# EC60_1.net
KiCad netlist of a schematic drawn in EAGLE
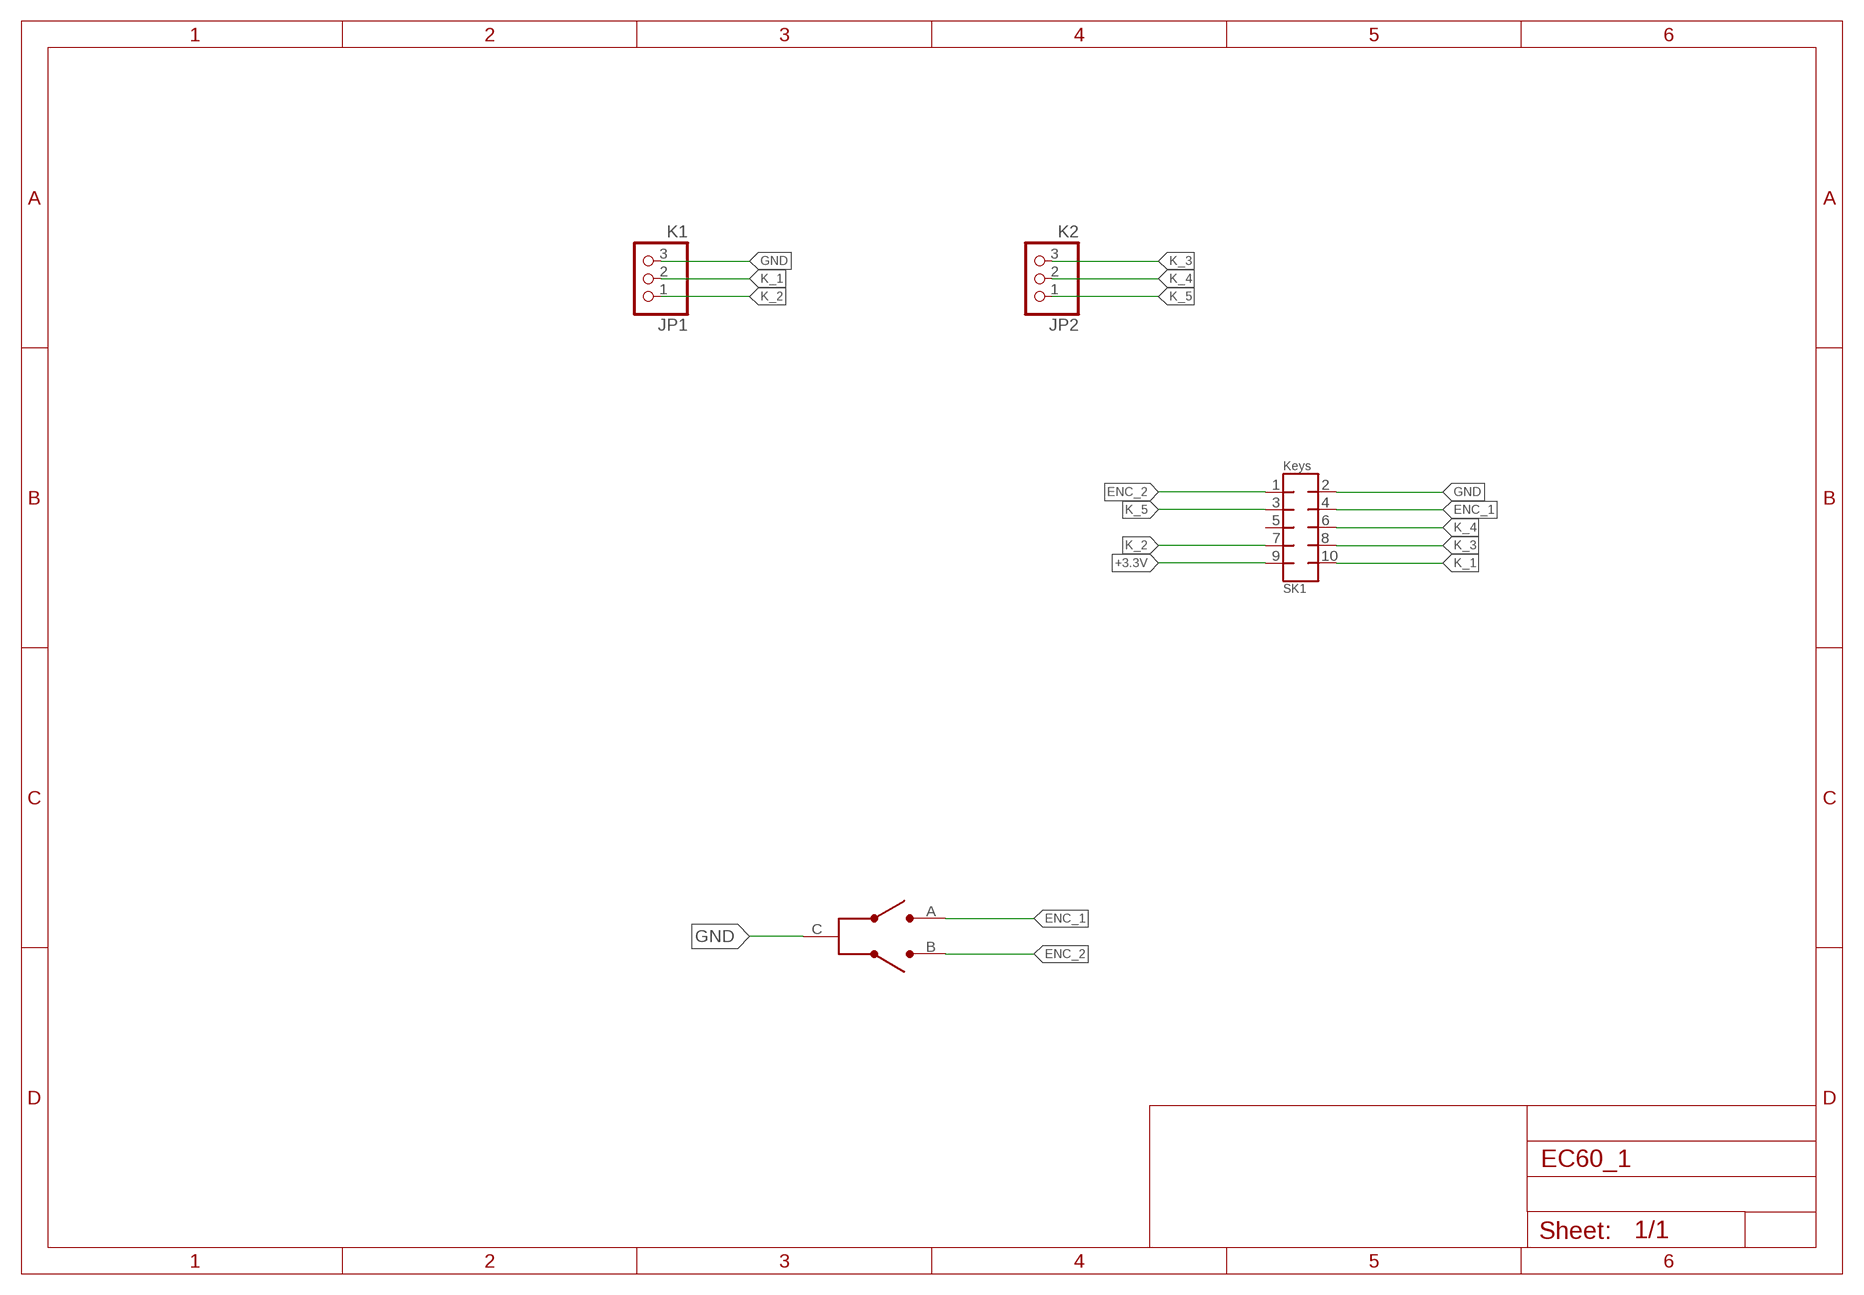
[diagram p0: schematic, sheet 1]

(export (version "E")
  (design (tool "Eeschema 10.0.6"))
  (components
    (comp (ref "JP1")
      (value "K1")
      (footprint "eagle-import:1X03")
      (libsource (lib "eagle-import") (part "PINHD-1X3"))
    )
    (comp (ref "JP2")
      (value "K2")
      (footprint "eagle-import:1X03")
      (libsource (lib "eagle-import") (part "PINHD-1X3"))
    )
    (comp (ref "SK1")
      (value "Keys")
      (footprint "eagle-import:AMP-215079-10")
      (libsource (lib "eagle-import") (part "MMATCH-10-PTH"))
    )
    (comp (ref "U$1")
      (value "EC60A")
      (footprint "eagle-import:EC60A")
      (libsource (lib "eagle-import") (part "EC60A"))
    )
  )
  (nets
    (net (code "1") (name "+3.3V") (class "Default")
      (node (ref "SK1") (pin "9") (pinfunction "9_9") (pintype "bidirectional"))
    )
    (net (code "2") (name "ENC_1") (class "Default")
      (node (ref "SK1") (pin "4") (pinfunction "4_4") (pintype "bidirectional"))
      (node (ref "U$1") (pin "A") (pinfunction "A_A") (pintype "passive"))
    )
    (net (code "3") (name "ENC_2") (class "Default")
      (node (ref "SK1") (pin "1") (pinfunction "1_1") (pintype "bidirectional"))
      (node (ref "U$1") (pin "B") (pinfunction "B_B") (pintype "passive"))
    )
    (net (code "4") (name "GND") (class "Default")
      (node (ref "JP1") (pin "3") (pinfunction "3_3") (pintype "passive"))
      (node (ref "SK1") (pin "2") (pinfunction "2_2") (pintype "bidirectional"))
      (node (ref "U$1") (pin "C") (pinfunction "C_C") (pintype "passive"))
    )
    (net (code "5") (name "K_1") (class "Default")
      (node (ref "JP1") (pin "2") (pinfunction "2_2") (pintype "passive"))
      (node (ref "SK1") (pin "10") (pinfunction "10_10") (pintype "bidirectional"))
    )
    (net (code "6") (name "K_2") (class "Default")
      (node (ref "JP1") (pin "1") (pinfunction "1_1") (pintype "passive"))
      (node (ref "SK1") (pin "7") (pinfunction "7_7") (pintype "bidirectional"))
    )
    (net (code "7") (name "K_3") (class "Default")
      (node (ref "JP2") (pin "3") (pinfunction "3_3") (pintype "passive"))
      (node (ref "SK1") (pin "8") (pinfunction "8_8") (pintype "bidirectional"))
    )
    (net (code "8") (name "K_4") (class "Default")
      (node (ref "JP2") (pin "2") (pinfunction "2_2") (pintype "passive"))
      (node (ref "SK1") (pin "6") (pinfunction "6_6") (pintype "bidirectional"))
    )
    (net (code "9") (name "K_5") (class "Default")
      (node (ref "JP2") (pin "1") (pinfunction "1_1") (pintype "passive"))
      (node (ref "SK1") (pin "3") (pinfunction "3_3") (pintype "bidirectional"))
    )
    (net (code "10") (name "unconnected-(SK1-Pad5)") (class "Default")
      (node (ref "SK1") (pin "5") (pinfunction "5_5") (pintype "bidirectional"))
    )
  )
)
